# main.net
KiCad netlist of a schematic drawn in Altium Designer
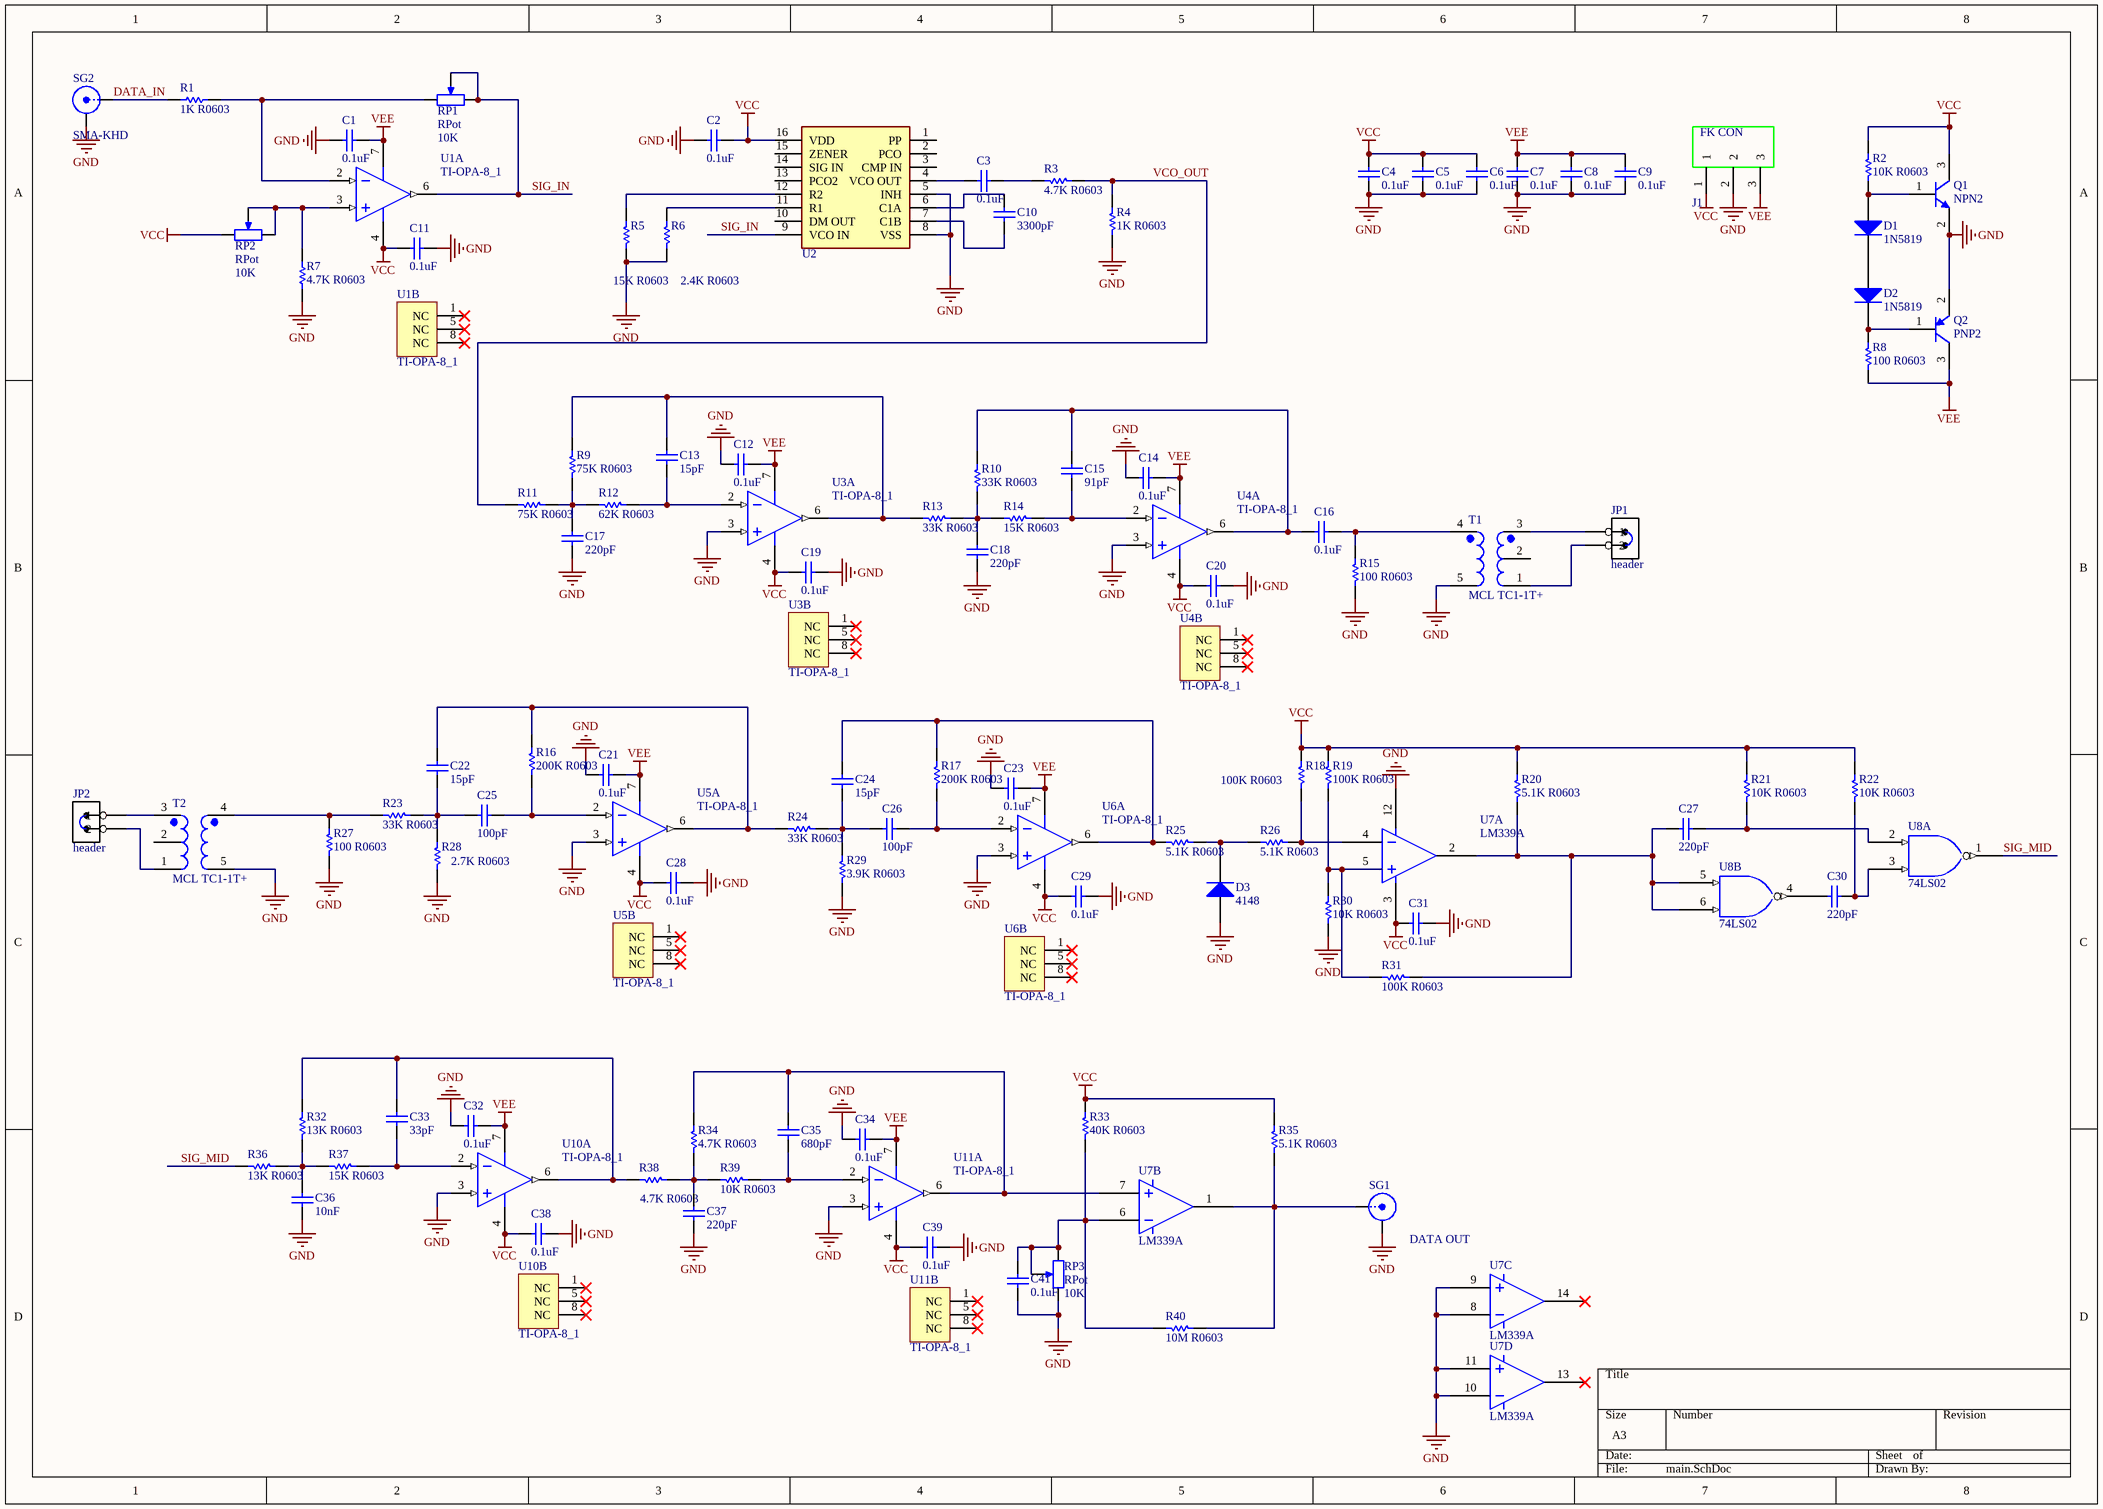
[diagram p0: main.SchDoc]

(export (version "E")
  (design (tool "Eeschema 10.0.6"))
  (components
    (comp (ref "C1")
      (value "0.1uF")
      (footprint "0603_C")
      (description "Capacitor")
      (fields (field (name "PUBLISHER") "Altium Limited"))
      (libsource (lib "My Footprint") (part "CAP"))
    )
    (comp (ref "C2")
      (value "0.1uF")
      (footprint "0603_C")
      (description "Capacitor")
      (fields (field (name "PUBLISHER") "Altium Limited"))
      (libsource (lib "My Footprint") (part "CAP"))
    )
    (comp (ref "C3")
      (value "0.1uF")
      (footprint "0603_C")
      (description "Capacitor")
      (fields (field (name "PUBLISHER") "Altium Limited"))
      (libsource (lib "My Footprint") (part "CAP"))
    )
    (comp (ref "C4")
      (value "0.1uF")
      (footprint "0603_C")
      (description "Capacitor")
      (fields (field (name "PUBLISHER") "Altium Limited"))
      (libsource (lib "My Footprint") (part "CAP"))
    )
    (comp (ref "C5")
      (value "0.1uF")
      (footprint "0603_C")
      (description "Capacitor")
      (fields (field (name "PUBLISHER") "Altium Limited"))
      (libsource (lib "My Footprint") (part "CAP"))
    )
    (comp (ref "C6")
      (value "0.1uF")
      (footprint "0603_C")
      (description "Capacitor")
      (fields (field (name "PUBLISHER") "Altium Limited"))
      (libsource (lib "My Footprint") (part "CAP"))
    )
    (comp (ref "C7")
      (value "0.1uF")
      (footprint "0603_C")
      (description "Capacitor")
      (fields (field (name "PUBLISHER") "Altium Limited"))
      (libsource (lib "My Footprint") (part "CAP"))
    )
    (comp (ref "C8")
      (value "0.1uF")
      (footprint "0603_C")
      (description "Capacitor")
      (fields (field (name "PUBLISHER") "Altium Limited"))
      (libsource (lib "My Footprint") (part "CAP"))
    )
    (comp (ref "C9")
      (value "0.1uF")
      (footprint "0603_C")
      (description "Capacitor")
      (fields (field (name "PUBLISHER") "Altium Limited"))
      (libsource (lib "My Footprint") (part "CAP"))
    )
    (comp (ref "C10")
      (value "3300pF")
      (footprint "0603_C")
      (description "Capacitor")
      (fields (field (name "PUBLISHER") "Altium Limited"))
      (libsource (lib "My Footprint") (part "CAP"))
    )
    (comp (ref "C11")
      (value "0.1uF")
      (footprint "0603_C")
      (description "Capacitor")
      (fields (field (name "PUBLISHER") "Altium Limited"))
      (libsource (lib "My Footprint") (part "CAP"))
    )
    (comp (ref "C12")
      (value "0.1uF")
      (footprint "0603_C")
      (description "Capacitor")
      (fields (field (name "PUBLISHER") "Altium Limited"))
      (libsource (lib "My Footprint") (part "CAP"))
    )
    (comp (ref "C13")
      (value "15pF")
      (footprint "0603_C")
      (description "Capacitor")
      (fields (field (name "PUBLISHER") "Altium Limited"))
      (libsource (lib "My Footprint") (part "CAP"))
    )
    (comp (ref "C14")
      (value "0.1uF")
      (footprint "0603_C")
      (description "Capacitor")
      (fields (field (name "PUBLISHER") "Altium Limited"))
      (libsource (lib "My Footprint") (part "CAP"))
    )
    (comp (ref "C15")
      (value "91pF")
      (footprint "0603_C")
      (description "Capacitor")
      (fields (field (name "PUBLISHER") "Altium Limited"))
      (libsource (lib "My Footprint") (part "CAP"))
    )
    (comp (ref "C16")
      (value "0.1uF")
      (footprint "0603_C")
      (description "Capacitor")
      (fields (field (name "PUBLISHER") "Altium Limited"))
      (libsource (lib "My Footprint") (part "CAP"))
    )
    (comp (ref "C17")
      (value "220pF")
      (footprint "0603_C")
      (description "Capacitor")
      (fields (field (name "PUBLISHER") "Altium Limited"))
      (libsource (lib "My Footprint") (part "CAP"))
    )
    (comp (ref "C18")
      (value "220pF")
      (footprint "0603_C")
      (description "Capacitor")
      (fields (field (name "PUBLISHER") "Altium Limited"))
      (libsource (lib "My Footprint") (part "CAP"))
    )
    (comp (ref "C19")
      (value "0.1uF")
      (footprint "0603_C")
      (description "Capacitor")
      (fields (field (name "PUBLISHER") "Altium Limited"))
      (libsource (lib "My Footprint") (part "CAP"))
    )
    (comp (ref "C20")
      (value "0.1uF")
      (footprint "0603_C")
      (description "Capacitor")
      (fields (field (name "PUBLISHER") "Altium Limited"))
      (libsource (lib "My Footprint") (part "CAP"))
    )
    (comp (ref "C21")
      (value "0.1uF")
      (footprint "0603_C")
      (description "Capacitor")
      (fields (field (name "PUBLISHER") "Altium Limited"))
      (libsource (lib "My Footprint") (part "CAP"))
    )
    (comp (ref "C22")
      (value "15pF")
      (footprint "0603_C")
      (description "Capacitor")
      (fields (field (name "PUBLISHER") "Altium Limited"))
      (libsource (lib "My Footprint") (part "CAP"))
    )
    (comp (ref "C23")
      (value "0.1uF")
      (footprint "0603_C")
      (description "Capacitor")
      (fields (field (name "PUBLISHER") "Altium Limited"))
      (libsource (lib "My Footprint") (part "CAP"))
    )
    (comp (ref "C24")
      (value "15pF")
      (footprint "0603_C")
      (description "Capacitor")
      (fields (field (name "PUBLISHER") "Altium Limited"))
      (libsource (lib "My Footprint") (part "CAP"))
    )
    (comp (ref "C25")
      (value "100pF")
      (footprint "0603_C")
      (description "Capacitor")
      (fields (field (name "PUBLISHER") "Altium Limited"))
      (libsource (lib "My Footprint") (part "CAP"))
    )
    (comp (ref "C26")
      (value "100pF")
      (footprint "0603_C")
      (description "Capacitor")
      (fields (field (name "PUBLISHER") "Altium Limited"))
      (libsource (lib "My Footprint") (part "CAP"))
    )
    (comp (ref "C27")
      (value "220pF")
      (footprint "0603_C")
      (description "Capacitor")
      (fields (field (name "PUBLISHER") "Altium Limited"))
      (libsource (lib "My Footprint") (part "CAP"))
    )
    (comp (ref "C28")
      (value "0.1uF")
      (footprint "0603_C")
      (description "Capacitor")
      (fields (field (name "PUBLISHER") "Altium Limited"))
      (libsource (lib "My Footprint") (part "CAP"))
    )
    (comp (ref "C29")
      (value "0.1uF")
      (footprint "0603_C")
      (description "Capacitor")
      (fields (field (name "PUBLISHER") "Altium Limited"))
      (libsource (lib "My Footprint") (part "CAP"))
    )
    (comp (ref "C30")
      (value "220pF")
      (footprint "0603_C")
      (description "Capacitor")
      (fields (field (name "PUBLISHER") "Altium Limited"))
      (libsource (lib "My Footprint") (part "CAP"))
    )
    (comp (ref "C31")
      (value "0.1uF")
      (footprint "0603_C")
      (description "Capacitor")
      (fields (field (name "PUBLISHER") "Altium Limited"))
      (libsource (lib "My Footprint") (part "CAP"))
    )
    (comp (ref "C32")
      (value "0.1uF")
      (footprint "0603_C")
      (description "Capacitor")
      (fields (field (name "PUBLISHER") "Altium Limited"))
      (libsource (lib "My Footprint") (part "CAP"))
    )
    (comp (ref "C33")
      (value "33pF")
      (footprint "0603_C")
      (description "Capacitor")
      (fields (field (name "PUBLISHER") "Altium Limited"))
      (libsource (lib "My Footprint") (part "CAP"))
    )
    (comp (ref "C34")
      (value "0.1uF")
      (footprint "0603_C")
      (description "Capacitor")
      (fields (field (name "PUBLISHER") "Altium Limited"))
      (libsource (lib "My Footprint") (part "CAP"))
    )
    (comp (ref "C35")
      (value "680pF")
      (footprint "0603_C")
      (description "Capacitor")
      (fields (field (name "PUBLISHER") "Altium Limited"))
      (libsource (lib "My Footprint") (part "CAP"))
    )
    (comp (ref "C36")
      (value "10nF")
      (footprint "0603_C")
      (description "Capacitor")
      (fields (field (name "PUBLISHER") "Altium Limited"))
      (libsource (lib "My Footprint") (part "CAP"))
    )
    (comp (ref "C37")
      (value "220pF")
      (footprint "0603_C")
      (description "Capacitor")
      (fields (field (name "PUBLISHER") "Altium Limited"))
      (libsource (lib "My Footprint") (part "CAP"))
    )
    (comp (ref "C38")
      (value "0.1uF")
      (footprint "0603_C")
      (description "Capacitor")
      (fields (field (name "PUBLISHER") "Altium Limited"))
      (libsource (lib "My Footprint") (part "CAP"))
    )
    (comp (ref "C39")
      (value "0.1uF")
      (footprint "0603_C")
      (description "Capacitor")
      (fields (field (name "PUBLISHER") "Altium Limited"))
      (libsource (lib "My Footprint") (part "CAP"))
    )
    (comp (ref "C41")
      (value "0.1uF")
      (footprint "0603_C")
      (description "Capacitor")
      (fields (field (name "PUBLISHER") "Altium Limited"))
      (libsource (lib "My Footprint") (part "CAP"))
    )
    (comp (ref "D1")
      (value "1N5819")
      (footprint "SOD123")
      (description "40V 1A PEAK 25a")
      (libsource (lib "My Footprint") (part "1N5819"))
    )
    (comp (ref "D2")
      (value "1N5819")
      (footprint "SOD123")
      (description "40V 1A PEAK 25a")
      (libsource (lib "My Footprint") (part "1N5819"))
    )
    (comp (ref "D3")
      (value "4148")
      (footprint "DIODE_SOIC")
      (description "High Conductance Fast Diode")
      (fields (field (name "PUBLISHER") "Altium Limited"))
      (libsource (lib "My Footprint") (part "1N4148"))
    )
    (comp (ref "J1")
      (value "FK_CONN_3PIN")
      (footprint "FK_CONN_3pin")
      (libsource (lib "My Footprint") (part "FK_CONN_3PIN"))
    )
    (comp (ref "JP1") (value "header") (footprint "header2") (libsource (lib "") (part "HEADER 2_1")))
    (comp (ref "JP2")
      (value "header")
      (footprint "header2")
      (libsource (lib "My Footprint") (part "HEADER 2"))
    )
    (comp (ref "Q1")
      (value "NPN2")
      (footprint "SOT-23-3")
      (description "贴片")
      (libsource (lib "My Footprint") (part "NPN2"))
    )
    (comp (ref "Q2")
      (value "PNP2")
      (footprint "SOT-23-3")
      (description "贴片")
      (fields (field (name "PUBLISHER") "Altium Limited"))
      (libsource (lib "My Footprint") (part "PNP2"))
    )
    (comp (ref "R1")
      (value "1K R0603")
      (footprint "0603_R")
      (description "Resistor")
      (fields (field (name "PUBLISHER") "Altium Limited"))
      (libsource (lib "My Footprint") (part "RES"))
    )
    (comp (ref "R2")
      (value "10K R0603")
      (footprint "0603_R")
      (description "Resistor")
      (fields (field (name "PUBLISHER") "Altium Limited"))
      (libsource (lib "My Footprint") (part "RES"))
    )
    (comp (ref "R3")
      (value "4.7K R0603")
      (footprint "0603_R")
      (description "Resistor")
      (fields (field (name "PUBLISHER") "Altium Limited"))
      (libsource (lib "My Footprint") (part "RES"))
    )
    (comp (ref "R4")
      (value "1K R0603")
      (footprint "0603_R")
      (description "Resistor")
      (fields (field (name "PUBLISHER") "Altium Limited"))
      (libsource (lib "My Footprint") (part "RES"))
    )
    (comp (ref "R5")
      (value "15K R0603")
      (footprint "0603_R")
      (description "Resistor")
      (fields (field (name "PUBLISHER") "Altium Limited"))
      (libsource (lib "My Footprint") (part "RES"))
    )
    (comp (ref "R6")
      (value "2.4K R0603")
      (footprint "0603_R")
      (description "Resistor")
      (fields (field (name "PUBLISHER") "Altium Limited"))
      (libsource (lib "My Footprint") (part "RES"))
    )
    (comp (ref "R7")
      (value "4.7K R0603")
      (footprint "0603_R")
      (description "Resistor")
      (fields (field (name "PUBLISHER") "Altium Limited"))
      (libsource (lib "My Footprint") (part "RES"))
    )
    (comp (ref "R8")
      (value "100 R0603")
      (footprint "0603_R")
      (description "Resistor")
      (fields (field (name "PUBLISHER") "Altium Limited"))
      (libsource (lib "My Footprint") (part "RES"))
    )
    (comp (ref "R9")
      (value "75K R0603")
      (footprint "0603_R")
      (description "Resistor")
      (fields (field (name "PUBLISHER") "Altium Limited"))
      (libsource (lib "My Footprint") (part "RES"))
    )
    (comp (ref "R10")
      (value "33K R0603")
      (footprint "0603_R")
      (description "Resistor")
      (fields (field (name "PUBLISHER") "Altium Limited"))
      (libsource (lib "My Footprint") (part "RES"))
    )
    (comp (ref "R11")
      (value "75K R0603")
      (footprint "0603_R")
      (description "Resistor")
      (fields (field (name "PUBLISHER") "Altium Limited"))
      (libsource (lib "My Footprint") (part "RES"))
    )
    (comp (ref "R12")
      (value "62K R0603")
      (footprint "0603_R")
      (description "Resistor")
      (fields (field (name "PUBLISHER") "Altium Limited"))
      (libsource (lib "My Footprint") (part "RES"))
    )
    (comp (ref "R13")
      (value "33K R0603")
      (footprint "0603_R")
      (description "Resistor")
      (fields (field (name "PUBLISHER") "Altium Limited"))
      (libsource (lib "My Footprint") (part "RES"))
    )
    (comp (ref "R14")
      (value "15K R0603")
      (footprint "0603_R")
      (description "Resistor")
      (fields (field (name "PUBLISHER") "Altium Limited"))
      (libsource (lib "My Footprint") (part "RES"))
    )
    (comp (ref "R15")
      (value "100 R0603")
      (footprint "0603_R")
      (description "Resistor")
      (fields (field (name "PUBLISHER") "Altium Limited"))
      (libsource (lib "My Footprint") (part "RES"))
    )
    (comp (ref "R16")
      (value "200K R0603")
      (footprint "0603_R")
      (description "Resistor")
      (fields (field (name "PUBLISHER") "Altium Limited"))
      (libsource (lib "My Footprint") (part "RES"))
    )
    (comp (ref "R17")
      (value "200K R0603")
      (footprint "0603_R")
      (description "Resistor")
      (fields (field (name "PUBLISHER") "Altium Limited"))
      (libsource (lib "My Footprint") (part "RES"))
    )
    (comp (ref "R18")
      (value "100K R0603")
      (footprint "0603_R")
      (description "Resistor")
      (fields (field (name "PUBLISHER") "Altium Limited"))
      (libsource (lib "My Footprint") (part "RES"))
    )
    (comp (ref "R19")
      (value "100K R0603")
      (footprint "0603_R")
      (description "Resistor")
      (fields (field (name "PUBLISHER") "Altium Limited"))
      (libsource (lib "My Footprint") (part "RES"))
    )
    (comp (ref "R20")
      (value "5.1K R0603")
      (footprint "0603_R")
      (description "Resistor")
      (fields (field (name "PUBLISHER") "Altium Limited"))
      (libsource (lib "My Footprint") (part "RES"))
    )
    (comp (ref "R21")
      (value "10K R0603")
      (footprint "0603_R")
      (description "Resistor")
      (fields (field (name "PUBLISHER") "Altium Limited"))
      (libsource (lib "My Footprint") (part "RES"))
    )
    (comp (ref "R22")
      (value "10K R0603")
      (footprint "0603_R")
      (description "Resistor")
      (fields (field (name "PUBLISHER") "Altium Limited"))
      (libsource (lib "My Footprint") (part "RES"))
    )
    (comp (ref "R23")
      (value "33K R0603")
      (footprint "0603_R")
      (description "Resistor")
      (fields (field (name "PUBLISHER") "Altium Limited"))
      (libsource (lib "My Footprint") (part "RES"))
    )
    (comp (ref "R24")
      (value "33K R0603")
      (footprint "0603_R")
      (description "Resistor")
      (fields (field (name "PUBLISHER") "Altium Limited"))
      (libsource (lib "My Footprint") (part "RES"))
    )
    (comp (ref "R25")
      (value "5.1K R0603")
      (footprint "0603_R")
      (description "Resistor")
      (fields (field (name "PUBLISHER") "Altium Limited"))
      (libsource (lib "My Footprint") (part "RES"))
    )
    (comp (ref "R26")
      (value "5.1K R0603")
      (footprint "0603_R")
      (description "Resistor")
      (fields (field (name "PUBLISHER") "Altium Limited"))
      (libsource (lib "My Footprint") (part "RES"))
    )
    (comp (ref "R27")
      (value "100 R0603")
      (footprint "0603_R")
      (description "Resistor")
      (fields (field (name "PUBLISHER") "Altium Limited"))
      (libsource (lib "My Footprint") (part "RES"))
    )
    (comp (ref "R28")
      (value "2.7K R0603")
      (footprint "0603_R")
      (description "Resistor")
      (fields (field (name "PUBLISHER") "Altium Limited"))
      (libsource (lib "My Footprint") (part "RES"))
    )
    (comp (ref "R29")
      (value "3.9K R0603")
      (footprint "0603_R")
      (description "Resistor")
      (fields (field (name "PUBLISHER") "Altium Limited"))
      (libsource (lib "My Footprint") (part "RES"))
    )
    (comp (ref "R30")
      (value "10K R0603")
      (footprint "0603_R")
      (description "Resistor")
      (fields (field (name "PUBLISHER") "Altium Limited"))
      (libsource (lib "My Footprint") (part "RES"))
    )
    (comp (ref "R31")
      (value "100K R0603")
      (footprint "0603_R")
      (description "Resistor")
      (fields (field (name "PUBLISHER") "Altium Limited"))
      (libsource (lib "My Footprint") (part "RES"))
    )
    (comp (ref "R32")
      (value "13K R0603")
      (footprint "0603_R")
      (description "Resistor")
      (fields (field (name "PUBLISHER") "Altium Limited"))
      (libsource (lib "My Footprint") (part "RES"))
    )
    (comp (ref "R33")
      (value "40K R0603")
      (footprint "0603_R")
      (description "Resistor")
      (fields (field (name "PUBLISHER") "Altium Limited"))
      (libsource (lib "My Footprint") (part "RES"))
    )
    (comp (ref "R34")
      (value "4.7K R0603")
      (footprint "0603_R")
      (description "Resistor")
      (fields (field (name "PUBLISHER") "Altium Limited"))
      (libsource (lib "My Footprint") (part "RES"))
    )
    (comp (ref "R35")
      (value "5.1K R0603")
      (footprint "0603_R")
      (description "Resistor")
      (fields (field (name "PUBLISHER") "Altium Limited"))
      (libsource (lib "My Footprint") (part "RES"))
    )
    (comp (ref "R36")
      (value "13K R0603")
      (footprint "0603_R")
      (description "Resistor")
      (fields (field (name "PUBLISHER") "Altium Limited"))
      (libsource (lib "My Footprint") (part "RES"))
    )
    (comp (ref "R37")
      (value "15K R0603")
      (footprint "0603_R")
      (description "Resistor")
      (fields (field (name "PUBLISHER") "Altium Limited"))
      (libsource (lib "My Footprint") (part "RES"))
    )
    (comp (ref "R38")
      (value "4.7K R0603")
      (footprint "0603_R")
      (description "Resistor")
      (fields (field (name "PUBLISHER") "Altium Limited"))
      (libsource (lib "My Footprint") (part "RES"))
    )
    (comp (ref "R39")
      (value "10K R0603")
      (footprint "0603_R")
      (description "Resistor")
      (fields (field (name "PUBLISHER") "Altium Limited"))
      (libsource (lib "My Footprint") (part "RES"))
    )
    (comp (ref "R40")
      (value "10M R0603")
      (footprint "0603_R")
      (description "Resistor")
      (fields (field (name "PUBLISHER") "Altium Limited"))
      (libsource (lib "My Footprint") (part "RES"))
    )
    (comp (ref "RP1")
      (value "RPot")
      (footprint "RPot")
      (description "Potentiometer")
      (fields (field (name "ALTIUM_VALUE") "10K") (field (name "PUBLISHER") "Altium Limited"))
      (libsource (lib "") (part "RPot_1"))
    )
    (comp (ref "RP2")
      (value "RPot")
      (footprint "RPot")
      (description "Potentiometer")
      (fields (field (name "ALTIUM_VALUE") "10K") (field (name "PUBLISHER") "Altium Limited"))
      (libsource (lib "") (part "RPot_1"))
    )
    (comp (ref "RP3")
      (value "RPot")
      (footprint "RPot")
      (description "Potentiometer")
      (fields (field (name "ALTIUM_VALUE") "10K") (field (name "PUBLISHER") "Altium Limited"))
      (libsource (lib "My Footprint") (part "RPot"))
    )
    (comp (ref "SG1")
      (value "DATA OUT")
      (footprint "SMA-2")
      (libsource (lib "My Footprint") (part "SMA_KHD"))
    )
    (comp (ref "SG2") (value "SMA-KHD") (footprint "SMA-2") (libsource (lib "My Footprint") (part "SMA_KHD")))
    (comp (ref "T1")
      (value "MCL TC1-1T+")
      (footprint "TC1-1T")
      (libsource (lib "My Footprint") (part "TC1-1T+"))
    )
    (comp (ref "T2") (value "MCL TC1-1T+") (footprint "TC1-1T") (libsource (lib "") (part "TC1-1T+_1")))
    (comp (ref "U1")
      (value "TI-OPA-8_1")
      (footprint "SOIC-8")
      (libsource (lib "My Footprint") (part "TI-OPA-8_1"))
    )
    (comp (ref "U2") (value "cd4046") (footprint "SOIC-16") (libsource (lib "SamacSys") (part "cd4046")))
    (comp (ref "U3")
      (value "TI-OPA-8_1")
      (footprint "SOIC-8")
      (libsource (lib "My Footprint") (part "TI-OPA-8_1"))
    )
    (comp (ref "U4")
      (value "TI-OPA-8_1")
      (footprint "SOIC-8")
      (libsource (lib "My Footprint") (part "TI-OPA-8_1"))
    )
    (comp (ref "U5")
      (value "TI-OPA-8_1")
      (footprint "SOIC-8")
      (libsource (lib "My Footprint") (part "TI-OPA-8_1"))
    )
    (comp (ref "U6")
      (value "TI-OPA-8_1")
      (footprint "SOIC-8")
      (libsource (lib "My Footprint") (part "TI-OPA-8_1"))
    )
    (comp (ref "U7") (value "LM339A") (footprint "SOIC-14") (libsource (lib "My Footprint") (part "LM339A")))
    (comp (ref "U8") (value "74LS02") (footprint "DIP-14") (libsource (lib "My Footprint") (part "74LS02")))
    (comp (ref "U10")
      (value "TI-OPA-8_1")
      (footprint "SOIC-8")
      (libsource (lib "My Footprint") (part "TI-OPA-8_1"))
    )
    (comp (ref "U11")
      (value "TI-OPA-8_1")
      (footprint "SOIC-8")
      (libsource (lib "My Footprint") (part "TI-OPA-8_1"))
    )
  )
  (nets
    (net (code "1") (name "/DATA_IN") (class "Default")
      (node (ref "R1") (pin "1") (pinfunction "1_1") (pintype "passive"))
      (node (ref "SG2") (pin "2") (pinfunction "X_2") (pintype "passive"))
    )
    (net (code "2") (name "/SIG_IN") (class "Default")
      (node (ref "RP1") (pin "1") (pinfunction "TOP_1") (pintype "passive"))
      (node (ref "RP1") (pin "2") (pinfunction "TAP_2") (pintype "passive"))
      (node (ref "U1") (pin "6") (pinfunction "OUT_6") (pintype "output"))
      (node (ref "U2") (pin "9") (pinfunction "VCO_IN_9") (pintype "passive"))
    )
    (net (code "3") (name "/SIG_MID") (class "Default")
      (node (ref "R36") (pin "2") (pinfunction "2_2") (pintype "passive"))
      (node (ref "U8") (pin "1") (pintype "output"))
    )
    (net (code "4") (name "/VCO_OUT") (class "Default")
      (node (ref "R11") (pin "2") (pinfunction "2_2") (pintype "passive"))
      (node (ref "R3") (pin "1") (pinfunction "1_1") (pintype "passive"))
      (node (ref "R4") (pin "1") (pinfunction "1_1") (pintype "passive"))
    )
    (net (code "5") (name "GND") (class "Default")
      (node (ref "C1") (pin "1") (pinfunction "1_1") (pintype "passive"))
      (node (ref "C11") (pin "2") (pinfunction "2_2") (pintype "passive"))
      (node (ref "C12") (pin "1") (pinfunction "1_1") (pintype "passive"))
      (node (ref "C14") (pin "1") (pinfunction "1_1") (pintype "passive"))
      (node (ref "C17") (pin "1") (pinfunction "1_1") (pintype "passive"))
      (node (ref "C18") (pin "1") (pinfunction "1_1") (pintype "passive"))
      (node (ref "C19") (pin "2") (pinfunction "2_2") (pintype "passive"))
      (node (ref "C2") (pin "1") (pinfunction "1_1") (pintype "passive"))
      (node (ref "C20") (pin "2") (pinfunction "2_2") (pintype "passive"))
      (node (ref "C21") (pin "1") (pinfunction "1_1") (pintype "passive"))
      (node (ref "C23") (pin "1") (pinfunction "1_1") (pintype "passive"))
      (node (ref "C28") (pin "2") (pinfunction "2_2") (pintype "passive"))
      (node (ref "C29") (pin "2") (pinfunction "2_2") (pintype "passive"))
      (node (ref "C31") (pin "2") (pinfunction "2_2") (pintype "passive"))
      (node (ref "C32") (pin "1") (pinfunction "1_1") (pintype "passive"))
      (node (ref "C34") (pin "1") (pinfunction "1_1") (pintype "passive"))
      (node (ref "C36") (pin "1") (pinfunction "1_1") (pintype "passive"))
      (node (ref "C37") (pin "1") (pinfunction "1_1") (pintype "passive"))
      (node (ref "C38") (pin "2") (pinfunction "2_2") (pintype "passive"))
      (node (ref "C39") (pin "2") (pinfunction "2_2") (pintype "passive"))
      (node (ref "C4") (pin "2") (pinfunction "2_2") (pintype "passive"))
      (node (ref "C41") (pin "1") (pinfunction "1_1") (pintype "passive"))
      (node (ref "C5") (pin "2") (pinfunction "2_2") (pintype "passive"))
      (node (ref "C6") (pin "2") (pinfunction "2_2") (pintype "passive"))
      (node (ref "C7") (pin "2") (pinfunction "2_2") (pintype "passive"))
      (node (ref "C8") (pin "2") (pinfunction "2_2") (pintype "passive"))
      (node (ref "C9") (pin "2") (pinfunction "2_2") (pintype "passive"))
      (node (ref "D3") (pin "1") (pinfunction "A_1") (pintype "passive"))
      (node (ref "J1") (pin "2") (pinfunction "2_2") (pintype "passive"))
      (node (ref "Q1") (pin "2") (pinfunction "E_2") (pintype "passive"))
      (node (ref "Q2") (pin "2") (pinfunction "E_2") (pintype "passive"))
      (node (ref "R15") (pin "2") (pinfunction "2_2") (pintype "passive"))
      (node (ref "R27") (pin "2") (pinfunction "2_2") (pintype "passive"))
      (node (ref "R28") (pin "2") (pinfunction "2_2") (pintype "passive"))
      (node (ref "R29") (pin "2") (pinfunction "2_2") (pintype "passive"))
      (node (ref "R30") (pin "2") (pinfunction "2_2") (pintype "passive"))
      (node (ref "R4") (pin "2") (pinfunction "2_2") (pintype "passive"))
      (node (ref "R5") (pin "1") (pinfunction "1_1") (pintype "passive"))
      (node (ref "R6") (pin "1") (pinfunction "1_1") (pintype "passive"))
      (node (ref "R7") (pin "1") (pinfunction "1_1") (pintype "passive"))
      (node (ref "RP3") (pin "3") (pinfunction "BOT_3") (pintype "passive"))
      (node (ref "SG1") (pin "1") (pinfunction "Y_1") (pintype "passive"))
      (node (ref "SG2") (pin "1") (pinfunction "Y_1") (pintype "passive"))
      (node (ref "T1") (pin "5") (pinfunction "5_5") (pintype "passive"))
      (node (ref "T2") (pin "5") (pinfunction "5_5") (pintype "passive"))
      (node (ref "U10") (pin "3") (pinfunction "IN+_3") (pintype "input"))
      (node (ref "U11") (pin "3") (pinfunction "IN+_3") (pintype "input"))
      (node (ref "U2") (pin "5") (pinfunction "INH_5") (pintype "passive"))
      (node (ref "U2") (pin "8") (pinfunction "VSS_8") (pintype "passive"))
      (node (ref "U3") (pin "3") (pinfunction "IN+_3") (pintype "input"))
      (node (ref "U4") (pin "3") (pinfunction "IN+_3") (pintype "input"))
      (node (ref "U5") (pin "3") (pinfunction "IN+_3") (pintype "input"))
      (node (ref "U6") (pin "3") (pinfunction "IN+_3") (pintype "input"))
      (node (ref "U7") (pin "10") (pintype "passive"))
      (node (ref "U7") (pin "11") (pintype "passive"))
      (node (ref "U7") (pin "12") (pintype "passive"))
      (node (ref "U7") (pin "8") (pintype "passive"))
      (node (ref "U7") (pin "9") (pintype "passive"))
    )
    (net (code "6") (name "Net-(C3-Pad1)") (class "Default")
      (node (ref "C3") (pin "1") (pinfunction "1_1") (pintype "passive"))
      (node (ref "R3") (pin "2") (pinfunction "2_2") (pintype "passive"))
    )
    (net (code "7") (name "Net-(C16-Pad2)") (class "Default")
      (node (ref "C16") (pin "2") (pinfunction "2_2") (pintype "passive"))
      (node (ref "R15") (pin "1") (pinfunction "1_1") (pintype "passive"))
      (node (ref "T1") (pin "4") (pinfunction "4_4") (pintype "passive"))
    )
    (net (code "8") (name "Net-(C17-Pad2)") (class "Default")
      (node (ref "C17") (pin "2") (pinfunction "2_2") (pintype "passive"))
      (node (ref "R11") (pin "1") (pinfunction "1_1") (pintype "passive"))
      (node (ref "R12") (pin "2") (pinfunction "2_2") (pintype "passive"))
      (node (ref "R9") (pin "2") (pinfunction "2_2") (pintype "passive"))
    )
    (net (code "9") (name "Net-(C18-Pad2)") (class "Default")
      (node (ref "C18") (pin "2") (pinfunction "2_2") (pintype "passive"))
      (node (ref "R10") (pin "2") (pinfunction "2_2") (pintype "passive"))
      (node (ref "R13") (pin "1") (pinfunction "1_1") (pintype "passive"))
      (node (ref "R14") (pin "2") (pinfunction "2_2") (pintype "passive"))
    )
    (net (code "10") (name "Net-(C22-Pad1)") (class "Default")
      (node (ref "C22") (pin "1") (pinfunction "1_1") (pintype "passive"))
      (node (ref "C25") (pin "2") (pinfunction "2_2") (pintype "passive"))
      (node (ref "R23") (pin "1") (pinfunction "1_1") (pintype "passive"))
      (node (ref "R28") (pin "1") (pinfunction "1_1") (pintype "passive"))
    )
    (net (code "11") (name "Net-(C24-Pad1)") (class "Default")
      (node (ref "C24") (pin "1") (pinfunction "1_1") (pintype "passive"))
      (node (ref "C26") (pin "2") (pinfunction "2_2") (pintype "passive"))
      (node (ref "R24") (pin "1") (pinfunction "1_1") (pintype "passive"))
      (node (ref "R29") (pin "1") (pinfunction "1_1") (pintype "passive"))
    )
    (net (code "12") (name "Net-(C27-Pad1)") (class "Default")
      (node (ref "C27") (pin "1") (pinfunction "1_1") (pintype "passive"))
      (node (ref "R20") (pin "2") (pinfunction "2_2") (pintype "passive"))
      (node (ref "R31") (pin "2") (pinfunction "2_2") (pintype "passive"))
      (node (ref "U7") (pin "2") (pintype "passive"))
      (node (ref "U8") (pin "5") (pintype "input"))
      (node (ref "U8") (pin "6") (pintype "input"))
    )
    (net (code "13") (name "Net-(C27-Pad2)") (class "Default")
      (node (ref "C27") (pin "2") (pinfunction "2_2") (pintype "passive"))
      (node (ref "R21") (pin "2") (pinfunction "2_2") (pintype "passive"))
      (node (ref "U8") (pin "2") (pintype "input"))
    )
    (net (code "14") (name "Net-(C30-Pad1)") (class "Default")
      (node (ref "C30") (pin "1") (pinfunction "1_1") (pintype "passive"))
      (node (ref "U8") (pin "4") (pintype "output"))
    )
    (net (code "15") (name "Net-(C30-Pad2)") (class "Default")
      (node (ref "C30") (pin "2") (pinfunction "2_2") (pintype "passive"))
      (node (ref "R22") (pin "2") (pinfunction "2_2") (pintype "passive"))
      (node (ref "U8") (pin "3") (pintype "input"))
    )
    (net (code "16") (name "Net-(C36-Pad2)") (class "Default")
      (node (ref "C36") (pin "2") (pinfunction "2_2") (pintype "passive"))
      (node (ref "R32") (pin "2") (pinfunction "2_2") (pintype "passive"))
      (node (ref "R36") (pin "1") (pinfunction "1_1") (pintype "passive"))
      (node (ref "R37") (pin "2") (pinfunction "2_2") (pintype "passive"))
    )
    (net (code "17") (name "Net-(C37-Pad2)") (class "Default")
      (node (ref "C37") (pin "2") (pinfunction "2_2") (pintype "passive"))
      (node (ref "R34") (pin "2") (pinfunction "2_2") (pintype "passive"))
      (node (ref "R38") (pin "1") (pinfunction "1_1") (pintype "passive"))
      (node (ref "R39") (pin "2") (pinfunction "2_2") (pintype "passive"))
    )
    (net (code "18") (name "Net-(D1-A)") (class "Default")
      (node (ref "D1") (pin "1") (pinfunction "A_1") (pintype "passive"))
      (node (ref "Q1") (pin "1") (pinfunction "B_1") (pintype "passive"))
      (node (ref "R2") (pin "2") (pinfunction "2_2") (pintype "passive"))
    )
    (net (code "19") (name "Net-(D1-K)") (class "Default")
      (node (ref "D1") (pin "2") (pinfunction "K_2") (pintype "passive"))
      (node (ref "D2") (pin "1") (pinfunction "A_1") (pintype "passive"))
    )
    (net (code "20") (name "Net-(D2-K)") (class "Default")
      (node (ref "D2") (pin "2") (pinfunction "K_2") (pintype "passive"))
      (node (ref "Q2") (pin "1") (pinfunction "B_1") (pintype "passive"))
      (node (ref "R8") (pin "1") (pinfunction "1_1") (pintype "passive"))
    )
    (net (code "21") (name "Net-(D3-K)") (class "Default")
      (node (ref "D3") (pin "2") (pinfunction "K_2") (pintype "passive"))
      (node (ref "R25") (pin "1") (pinfunction "1_1") (pintype "passive"))
      (node (ref "R26") (pin "2") (pinfunction "2_2") (pintype "passive"))
    )
    (net (code "22") (name "Net-(JP1-Pad1)") (class "Default")
      (node (ref "JP1") (pin "1") (pinfunction "1_1") (pintype "passive"))
      (node (ref "T1") (pin "3") (pinfunction "3_3") (pintype "passive"))
    )
    (net (code "23") (name "Net-(JP1-Pad2)") (class "Default")
      (node (ref "JP1") (pin "2") (pinfunction "2_2") (pintype "passive"))
      (node (ref "T1") (pin "1") (pinfunction "1_1") (pintype "passive"))
    )
    (net (code "24") (name "Net-(JP2-Pad1)") (class "Default")
      (node (ref "JP2") (pin "1") (pinfunction "1_1") (pintype "passive"))
      (node (ref "T2") (pin "3") (pinfunction "3_3") (pintype "passive"))
    )
    (net (code "25") (name "Net-(JP2-Pad2)") (class "Default")
      (node (ref "JP2") (pin "2") (pinfunction "2_2") (pintype "passive"))
      (node (ref "T2") (pin "1") (pinfunction "1_1") (pintype "passive"))
    )
    (net (code "26") (name "Net-(R18-Pad2)") (class "Default")
      (node (ref "R18") (pin "2") (pinfunction "2_2") (pintype "passive"))
      (node (ref "R26") (pin "1") (pinfunction "1_1") (pintype "passive"))
      (node (ref "U7") (pin "4") (pintype "passive"))
    )
    (net (code "27") (name "Net-(R19-Pad2)") (class "Default")
      (node (ref "R19") (pin "2") (pinfunction "2_2") (pintype "passive"))
      (node (ref "R30") (pin "1") (pinfunction "1_1") (pintype "passive"))
      (node (ref "R31") (pin "1") (pinfunction "1_1") (pintype "passive"))
      (node (ref "U7") (pin "5") (pintype "passive"))
    )
    (net (code "28") (name "Net-(R23-Pad2)") (class "Default")
      (node (ref "R23") (pin "2") (pinfunction "2_2") (pintype "passive"))
      (node (ref "R27") (pin "1") (pinfunction "1_1") (pintype "passive"))
      (node (ref "T2") (pin "4") (pinfunction "4_4") (pintype "passive"))
    )
    (net (code "29") (name "Net-(RP1-BOT)") (class "Default")
      (node (ref "R1") (pin "2") (pinfunction "2_2") (pintype "passive"))
      (node (ref "RP1") (pin "3") (pinfunction "BOT_3") (pintype "passive"))
      (node (ref "U1") (pin "2") (pinfunction "IN-_2") (pintype "input"))
    )
    (net (code "30") (name "Net-(RP2-TAP)") (class "Default")
      (node (ref "R7") (pin "2") (pinfunction "2_2") (pintype "passive"))
      (node (ref "RP2") (pin "1") (pinfunction "TOP_1") (pintype "passive"))
      (node (ref "RP2") (pin "2") (pinfunction "TAP_2") (pintype "passive"))
      (node (ref "U1") (pin "3") (pinfunction "IN+_3") (pintype "input"))
    )
    (net (code "31") (name "Net-(RP3-TAP)") (class "Default")
      (node (ref "C41") (pin "2") (pinfunction "2_2") (pintype "passive"))
      (node (ref "R33") (pin "2") (pinfunction "2_2") (pintype "passive"))
      (node (ref "R40") (pin "1") (pinfunction "1_1") (pintype "passive"))
      (node (ref "RP3") (pin "1") (pinfunction "TOP_1") (pintype "passive"))
      (node (ref "RP3") (pin "2") (pinfunction "TAP_2") (pintype "passive"))
      (node (ref "U7") (pin "6") (pintype "passive"))
    )
    (net (code "32") (name "Net-(SG1-X)") (class "Default")
      (node (ref "R35") (pin "2") (pinfunction "2_2") (pintype "passive"))
      (node (ref "R40") (pin "2") (pinfunction "2_2") (pintype "passive"))
      (node (ref "SG1") (pin "2") (pinfunction "X_2") (pintype "passive"))
      (node (ref "U7") (pin "1") (pintype "passive"))
    )
    (net (code "33") (name "Net-(U2-C1A)") (class "Default")
      (node (ref "C10") (pin "2") (pinfunction "2_2") (pintype "passive"))
      (node (ref "U2") (pin "6") (pinfunction "C1A_6") (pintype "passive"))
    )
    (net (code "34") (name "Net-(U2-C1B)") (class "Default")
      (node (ref "C10") (pin "1") (pinfunction "1_1") (pintype "passive"))
      (node (ref "U2") (pin "7") (pinfunction "C1B_7") (pintype "passive"))
    )
    (net (code "35") (name "Net-(U2-R1)") (class "Default")
      (node (ref "R6") (pin "2") (pinfunction "2_2") (pintype "passive"))
      (node (ref "U2") (pin "11") (pinfunction "R1_11") (pintype "passive"))
    )
    (net (code "36") (name "Net-(U2-R2)") (class "Default")
      (node (ref "R5") (pin "2") (pinfunction "2_2") (pintype "passive"))
      (node (ref "U2") (pin "12") (pinfunction "R2_12") (pintype "passive"))
    )
    (net (code "37") (name "Net-(U2-VCO_OUT)") (class "Default")
      (node (ref "C3") (pin "2") (pinfunction "2_2") (pintype "passive"))
      (node (ref "U2") (pin "4") (pinfunction "VCO_OUT_4") (pintype "passive"))
    )
    (net (code "38") (name "Net-(U3A-IN-)") (class "Default")
      (node (ref "C13") (pin "1") (pinfunction "1_1") (pintype "passive"))
      (node (ref "R12") (pin "1") (pinfunction "1_1") (pintype "passive"))
      (node (ref "U3") (pin "2") (pinfunction "IN-_2") (pintype "input"))
    )
    (net (code "39") (name "Net-(U3A-OUT)") (class "Default")
      (node (ref "C13") (pin "2") (pinfunction "2_2") (pintype "passive"))
      (node (ref "R13") (pin "2") (pinfunction "2_2") (pintype "passive"))
      (node (ref "R9") (pin "1") (pinfunction "1_1") (pintype "passive"))
      (node (ref "U3") (pin "6") (pinfunction "OUT_6") (pintype "output"))
    )
    (net (code "40") (name "Net-(U4A-IN-)") (class "Default")
      (node (ref "C15") (pin "1") (pinfunction "1_1") (pintype "passive"))
      (node (ref "R14") (pin "1") (pinfunction "1_1") (pintype "passive"))
      (node (ref "U4") (pin "2") (pinfunction "IN-_2") (pintype "input"))
    )
    (net (code "41") (name "Net-(U4A-OUT)") (class "Default")
      (node (ref "C15") (pin "2") (pinfunction "2_2") (pintype "passive"))
      (node (ref "C16") (pin "1") (pinfunction "1_1") (pintype "passive"))
      (node (ref "R10") (pin "1") (pinfunction "1_1") (pintype "passive"))
      (node (ref "U4") (pin "6") (pinfunction "OUT_6") (pintype "output"))
    )
    (net (code "42") (name "Net-(U5A-IN-)") (class "Default")
      (node (ref "C25") (pin "1") (pinfunction "1_1") (pintype "passive"))
      (node (ref "R16") (pin "2") (pinfunction "2_2") (pintype "passive"))
      (node (ref "U5") (pin "2") (pinfunction "IN-_2") (pintype "input"))
    )
    (net (code "43") (name "Net-(U5A-OUT)") (class "Default")
      (node (ref "C22") (pin "2") (pinfunction "2_2") (pintype "passive"))
      (node (ref "R16") (pin "1") (pinfunction "1_1") (pintype "passive"))
      (node (ref "R24") (pin "2") (pinfunction "2_2") (pintype "passive"))
      (node (ref "U5") (pin "6") (pinfunction "OUT_6") (pintype "output"))
    )
    (net (code "44") (name "Net-(U6A-IN-)") (class "Default")
      (node (ref "C26") (pin "1") (pinfunction "1_1") (pintype "passive"))
      (node (ref "R17") (pin "2") (pinfunction "2_2") (pintype "passive"))
      (node (ref "U6") (pin "2") (pinfunction "IN-_2") (pintype "input"))
    )
    (net (code "45") (name "Net-(U6A-OUT)") (class "Default")
      (node (ref "C24") (pin "2") (pinfunction "2_2") (pintype "passive"))
      (node (ref "R17") (pin "1") (pinfunction "1_1") (pintype "passive"))
      (node (ref "R25") (pin "2") (pinfunction "2_2") (pintype "passive"))
      (node (ref "U6") (pin "6") (pinfunction "OUT_6") (pintype "output"))
    )
    (net (code "46") (name "Net-(U10A-IN-)") (class "Default")
      (node (ref "C33") (pin "1") (pinfunction "1_1") (pintype "passive"))
      (node (ref "R37") (pin "1") (pinfunction "1_1") (pintype "passive"))
      (node (ref "U10") (pin "2") (pinfunction "IN-_2") (pintype "input"))
    )
    (net (code "47") (name "Net-(U10A-OUT)") (class "Default")
      (node (ref "C33") (pin "2") (pinfunction "2_2") (pintype "passive"))
      (node (ref "R32") (pin "1") (pinfunction "1_1") (pintype "passive"))
      (node (ref "R38") (pin "2") (pinfunction "2_2") (pintype "passive"))
      (node (ref "U10") (pin "6") (pinfunction "OUT_6") (pintype "output"))
    )
    (net (code "48") (name "Net-(U11A-IN-)") (class "Default")
      (node (ref "C35") (pin "1") (pinfunction "1_1") (pintype "passive"))
      (node (ref "R39") (pin "1") (pinfunction "1_1") (pintype "passive"))
      (node (ref "U11") (pin "2") (pinfunction "IN-_2") (pintype "input"))
    )
    (net (code "49") (name "Net-(U11A-OUT)") (class "Default")
      (node (ref "C35") (pin "2") (pinfunction "2_2") (pintype "passive"))
      (node (ref "R34") (pin "1") (pinfunction "1_1") (pintype "passive"))
      (node (ref "U11") (pin "6") (pinfunction "OUT_6") (pintype "output"))
      (node (ref "U7") (pin "7") (pintype "passive"))
    )
    (net (code "50") (name "VCC") (class "Default")
      (node (ref "C11") (pin "1") (pinfunction "1_1") (pintype "passive"))
      (node (ref "C19") (pin "1") (pinfunction "1_1") (pintype "passive"))
      (node (ref "C2") (pin "2") (pinfunction "2_2") (pintype "passive"))
      (node (ref "C20") (pin "1") (pinfunction "1_1") (pintype "passive"))
      (node (ref "C28") (pin "1") (pinfunction "1_1") (pintype "passive"))
      (node (ref "C29") (pin "1") (pinfunction "1_1") (pintype "passive"))
      (node (ref "C31") (pin "1") (pinfunction "1_1") (pintype "passive"))
      (node (ref "C38") (pin "1") (pinfunction "1_1") (pintype "passive"))
      (node (ref "C39") (pin "1") (pinfunction "1_1") (pintype "passive"))
      (node (ref "C4") (pin "1") (pinfunction "1_1") (pintype "passive"))
      (node (ref "C5") (pin "1") (pinfunction "1_1") (pintype "passive"))
      (node (ref "C6") (pin "1") (pinfunction "1_1") (pintype "passive"))
      (node (ref "J1") (pin "1") (pinfunction "1_1") (pintype "passive"))
      (node (ref "Q1") (pin "3") (pinfunction "C_3") (pintype "passive"))
      (node (ref "R18") (pin "1") (pinfunction "1_1") (pintype "passive"))
      (node (ref "R19") (pin "1") (pinfunction "1_1") (pintype "passive"))
      (node (ref "R2") (pin "1") (pinfunction "1_1") (pintype "passive"))
      (node (ref "R20") (pin "1") (pinfunction "1_1") (pintype "passive"))
      (node (ref "R21") (pin "1") (pinfunction "1_1") (pintype "passive"))
      (node (ref "R22") (pin "1") (pinfunction "1_1") (pintype "passive"))
      (node (ref "R33") (pin "1") (pinfunction "1_1") (pintype "passive"))
      (node (ref "R35") (pin "1") (pinfunction "1_1") (pintype "passive"))
      (node (ref "RP2") (pin "3") (pinfunction "BOT_3") (pintype "passive"))
      (node (ref "U1") (pin "4") (pinfunction "V-_4") (pintype "power_in"))
      (node (ref "U10") (pin "4") (pinfunction "V-_4") (pintype "power_in"))
      (node (ref "U11") (pin "4") (pinfunction "V-_4") (pintype "power_in"))
      (node (ref "U2") (pin "16") (pinfunction "VDD_16") (pintype "passive"))
      (node (ref "U3") (pin "4") (pinfunction "V-_4") (pintype "power_in"))
      (node (ref "U4") (pin "4") (pinfunction "V-_4") (pintype "power_in"))
      (node (ref "U5") (pin "4") (pinfunction "V-_4") (pintype "power_in"))
      (node (ref "U6") (pin "4") (pinfunction "V-_4") (pintype "power_in"))
      (node (ref "U7") (pin "3") (pintype "passive"))
    )
    (net (code "51") (name "VEE") (class "Default")
      (node (ref "C1") (pin "2") (pinfunction "2_2") (pintype "passive"))
      (node (ref "C12") (pin "2") (pinfunction "2_2") (pintype "passive"))
      (node (ref "C14") (pin "2") (pinfunction "2_2") (pintype "passive"))
      (node (ref "C21") (pin "2") (pinfunction "2_2") (pintype "passive"))
      (node (ref "C23") (pin "2") (pinfunction "2_2") (pintype "passive"))
      (node (ref "C32") (pin "2") (pinfunction "2_2") (pintype "passive"))
      (node (ref "C34") (pin "2") (pinfunction "2_2") (pintype "passive"))
      (node (ref "C7") (pin "1") (pinfunction "1_1") (pintype "passive"))
      (node (ref "C8") (pin "1") (pinfunction "1_1") (pintype "passive"))
      (node (ref "C9") (pin "1") (pinfunction "1_1") (pintype "passive"))
      (node (ref "J1") (pin "3") (pinfunction "3_3") (pintype "passive"))
      (node (ref "Q2") (pin "3") (pinfunction "C_3") (pintype "passive"))
      (node (ref "R8") (pin "2") (pinfunction "2_2") (pintype "passive"))
      (node (ref "U1") (pin "7") (pinfunction "V+_7") (pintype "power_in"))
      (node (ref "U10") (pin "7") (pinfunction "V+_7") (pintype "power_in"))
      (node (ref "U11") (pin "7") (pinfunction "V+_7") (pintype "power_in"))
      (node (ref "U3") (pin "7") (pinfunction "V+_7") (pintype "power_in"))
      (node (ref "U4") (pin "7") (pinfunction "V+_7") (pintype "power_in"))
      (node (ref "U5") (pin "7") (pinfunction "V+_7") (pintype "power_in"))
      (node (ref "U6") (pin "7") (pinfunction "V+_7") (pintype "power_in"))
    )
    (net (code "52") (name "unconnected-(T1-Pad2)") (class "Default")
      (node (ref "T1") (pin "2") (pinfunction "2_2") (pintype "passive"))
    )
    (net (code "53") (name "unconnected-(T2-Pad2)") (class "Default")
      (node (ref "T2") (pin "2") (pinfunction "2_2") (pintype "passive"))
    )
    (net (code "54") (name "unconnected-(U1B-NC-Pad1)") (class "Default")
      (node (ref "U1") (pin "1") (pinfunction "NC_1") (pintype "passive+no_connect"))
    )
    (net (code "55") (name "unconnected-(U1B-NC-Pad5)") (class "Default")
      (node (ref "U1") (pin "5") (pinfunction "NC_5") (pintype "passive+no_connect"))
    )
    (net (code "56") (name "unconnected-(U1B-NC-Pad8)") (class "Default")
      (node (ref "U1") (pin "8") (pinfunction "NC_8") (pintype "passive+no_connect"))
    )
    (net (code "57") (name "unconnected-(U2-CMP_IN-Pad3)") (class "Default")
      (node (ref "U2") (pin "3") (pinfunction "CMP_IN_3") (pintype "passive"))
    )
    (net (code "58") (name "unconnected-(U2-DM_OUT-Pad10)") (class "Default")
      (node (ref "U2") (pin "10") (pinfunction "DM_OUT_10") (pintype "passive"))
    )
    (net (code "59") (name "unconnected-(U2-PCO-Pad2)") (class "Default")
      (node (ref "U2") (pin "2") (pinfunction "PCO_2") (pintype "passive"))
    )
    (net (code "60") (name "unconnected-(U2-PCO2-Pad13)") (class "Default")
      (node (ref "U2") (pin "13") (pinfunction "PCO2_13") (pintype "passive"))
    )
    (net (code "61") (name "unconnected-(U2-PP-Pad1)") (class "Default")
      (node (ref "U2") (pin "1") (pinfunction "PP_1") (pintype "passive"))
    )
    (net (code "62") (name "unconnected-(U2-SIG_IN-Pad14)") (class "Default")
      (node (ref "U2") (pin "14") (pinfunction "SIG_IN_14") (pintype "passive"))
    )
    (net (code "63") (name "unconnected-(U2-ZENER-Pad15)") (class "Default")
      (node (ref "U2") (pin "15") (pinfunction "ZENER_15") (pintype "passive"))
    )
    (net (code "64") (name "unconnected-(U3B-NC-Pad1)") (class "Default")
      (node (ref "U3") (pin "1") (pinfunction "NC_1") (pintype "passive+no_connect"))
    )
    (net (code "65") (name "unconnected-(U3B-NC-Pad5)") (class "Default")
      (node (ref "U3") (pin "5") (pinfunction "NC_5") (pintype "passive+no_connect"))
    )
    (net (code "66") (name "unconnected-(U3B-NC-Pad8)") (class "Default")
      (node (ref "U3") (pin "8") (pinfunction "NC_8") (pintype "passive+no_connect"))
    )
    (net (code "67") (name "unconnected-(U4B-NC-Pad1)") (class "Default")
      (node (ref "U4") (pin "1") (pinfunction "NC_1") (pintype "passive+no_connect"))
    )
    (net (code "68") (name "unconnected-(U4B-NC-Pad5)") (class "Default")
      (node (ref "U4") (pin "5") (pinfunction "NC_5") (pintype "passive+no_connect"))
    )
    (net (code "69") (name "unconnected-(U4B-NC-Pad8)") (class "Default")
      (node (ref "U4") (pin "8") (pinfunction "NC_8") (pintype "passive+no_connect"))
    )
    (net (code "70") (name "unconnected-(U5B-NC-Pad1)") (class "Default")
      (node (ref "U5") (pin "1") (pinfunction "NC_1") (pintype "passive+no_connect"))
    )
    (net (code "71") (name "unconnected-(U5B-NC-Pad5)") (class "Default")
      (node (ref "U5") (pin "5") (pinfunction "NC_5") (pintype "passive+no_connect"))
    )
    (net (code "72") (name "unconnected-(U5B-NC-Pad8)") (class "Default")
      (node (ref "U5") (pin "8") (pinfunction "NC_8") (pintype "passive+no_connect"))
    )
    (net (code "73") (name "unconnected-(U6B-NC-Pad1)") (class "Default")
      (node (ref "U6") (pin "1") (pinfunction "NC_1") (pintype "passive+no_connect"))
    )
    (net (code "74") (name "unconnected-(U6B-NC-Pad5)") (class "Default")
      (node (ref "U6") (pin "5") (pinfunction "NC_5") (pintype "passive+no_connect"))
    )
    (net (code "75") (name "unconnected-(U6B-NC-Pad8)") (class "Default")
      (node (ref "U6") (pin "8") (pinfunction "NC_8") (pintype "passive+no_connect"))
    )
    (net (code "76") (name "unconnected-(U7-Pad13)") (class "Default")
      (node (ref "U7") (pin "13") (pintype "passive+no_connect"))
    )
    (net (code "77") (name "unconnected-(U7-Pad14)") (class "Default")
      (node (ref "U7") (pin "14") (pintype "passive+no_connect"))
    )
    (net (code "78") (name "unconnected-(U10B-NC-Pad1)") (class "Default")
      (node (ref "U10") (pin "1") (pinfunction "NC_1") (pintype "passive+no_connect"))
    )
    (net (code "79") (name "unconnected-(U10B-NC-Pad5)") (class "Default")
      (node (ref "U10") (pin "5") (pinfunction "NC_5") (pintype "passive+no_connect"))
    )
    (net (code "80") (name "unconnected-(U10B-NC-Pad8)") (class "Default")
      (node (ref "U10") (pin "8") (pinfunction "NC_8") (pintype "passive+no_connect"))
    )
    (net (code "81") (name "unconnected-(U11B-NC-Pad1)") (class "Default")
      (node (ref "U11") (pin "1") (pinfunction "NC_1") (pintype "passive+no_connect"))
    )
    (net (code "82") (name "unconnected-(U11B-NC-Pad5)") (class "Default")
      (node (ref "U11") (pin "5") (pinfunction "NC_5") (pintype "passive+no_connect"))
    )
    (net (code "83") (name "unconnected-(U11B-NC-Pad8)") (class "Default")
      (node (ref "U11") (pin "8") (pinfunction "NC_8") (pintype "passive+no_connect"))
    )
  )
)
